# Motores.net
KiCad netlist of a schematic drawn in Altium Designer
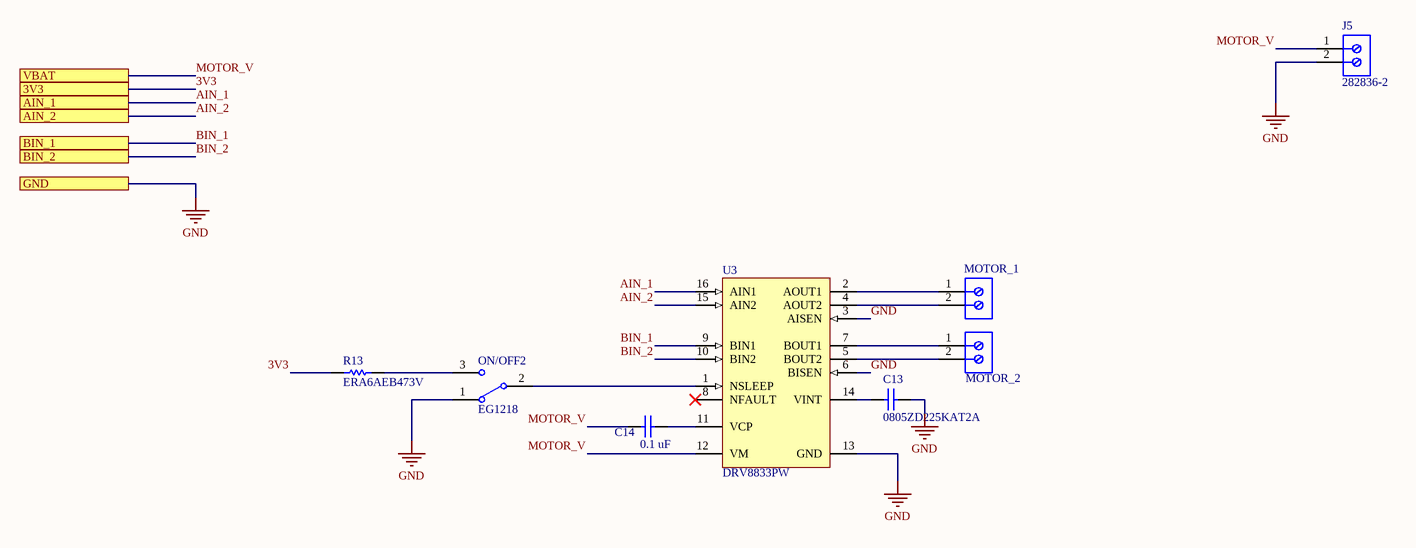
[diagram p0: Motores.SchDoc]

(export (version "E")
  (design (tool "Eeschema 10.0.6"))
  (components
    (comp (ref "C13")
      (value "0805ZD225KAT2A")
      (footprint "CAPC2013X140X50ML20T25")
      (description "Chip Capacitor, 2.2 uF, +/- 10%, 10 V, -55 to 85 degC, 0805 (2012 Metric), RoHS, Tape and Reel")
      (fields (field (name "MANUFACTURER") "AVX"))
      (libsource (lib "Altium Content Vault") (part "CAP-NP-2"))
    )
    (comp (ref "C14")
      (value "0.1 uF")
      (footprint "CAPC2013X94X50ML20T25")
      (description "Chip Capacitor, Ceramic, 0.1 uF, 10%, 50 V, 0805, RoHS, Tape and Reel")
      (fields (field (name "MANUFACTURER") "AVX"))
      (libsource (lib "Altium Content Vault") (part "CAP-NP-2"))
    )
    (comp (ref "J5")
      (value "282836-2")
      (footprint "TECO-282836-2_V")
      (description "Female Header, Pitch 5 mm, 1 x 2 Position, Height 10 mm, Tail Length 3.5 mm, Rohs, Bulk")
      (fields (field (name "VOLTAGE") "300V") (field (name "MANUFACTURER") "TE Connectivity"))
      (libsource (lib "Altium Content Vault") (part "CN-1P-F-TB2"))
    )
    (comp (ref "MOTOR_1")
      (value "691214110002")
      (footprint "691214110002")
      (description "Serie 2141 - 3.50 mm Horizontal Entry Modular with Rising Cage Clamp WR-TBL, 2 pin")
      (fields (field (name "MANUFACTURER") "Wurth Elektronik") (field (name "PUBLISHER") "WurthElektronik"))
      (libsource (lib "Altium Content Vault") (part "WE-CN-1P-F-TB2"))
    )
    (comp (ref "MOTOR_2")
      (value "691214110002")
      (footprint "691214110002")
      (description "Serie 2141 - 3.50 mm Horizontal Entry Modular with Rising Cage Clamp WR-TBL, 2 pin")
      (fields (field (name "MANUFACTURER") "Wurth Elektronik") (field (name "PUBLISHER") "WurthElektronik"))
      (libsource (lib "Altium Content Vault") (part "WE-CN-1P-F-TB2"))
    )
    (comp (ref "ON/OFF2")
      (value "EG1218")
      (footprint "ESWI-EG1218_V")
      (description "Slide Switch, 500 V, -20 to 70 degC, 3-Pin THD, RoHS")
      (libsource (lib "Altium Content Vault") (part "SW-SPDT-3_B"))
    )
    (comp (ref "R13")
      (value "ERA6AEB473V")
      (footprint "RESC2013X60X40LL20T25")
      (fields (field (name "MANUFACTURER") "Panasonic"))
      (libsource (lib "Altium Content Vault") (part "RES"))
    )
    (comp (ref "U3")
      (value "DRV8833PW")
      (footprint "PW0016A_M")
      (fields (field (name "MANUFACTURER") "Texas Instruments"))
      (libsource (lib "Altium Content Vault") (part "TI-DRV8833PW-16"))
    )
  )
  (nets
    (net (code "1") (name "/3V3") (class "Default")
      (node (ref "R13") (pin "2") (pinfunction "2_2") (pintype "passive"))
    )
    (net (code "2") (name "/AIN_1") (class "Default")
      (node (ref "U3") (pin "16") (pinfunction "AIN1_16") (pintype "input"))
    )
    (net (code "3") (name "/AIN_2") (class "Default")
      (node (ref "U3") (pin "15") (pinfunction "AIN2_15") (pintype "input"))
    )
    (net (code "4") (name "/BIN_1") (class "Default")
      (node (ref "U3") (pin "9") (pinfunction "BIN1_9") (pintype "input"))
    )
    (net (code "5") (name "/BIN_2") (class "Default")
      (node (ref "U3") (pin "10") (pinfunction "BIN2_10") (pintype "input"))
    )
    (net (code "6") (name "/MOTOR_V") (class "Default")
      (node (ref "C14") (pin "2") (pinfunction "2_2") (pintype "passive"))
      (node (ref "J5") (pin "1") (pinfunction "1_1") (pintype "passive"))
      (node (ref "U3") (pin "12") (pinfunction "VM_12") (pintype "power_in"))
    )
    (net (code "7") (name "GND") (class "Default")
      (node (ref "C13") (pin "2") (pinfunction "2_2") (pintype "passive"))
      (node (ref "J5") (pin "2") (pinfunction "2_2") (pintype "passive"))
      (node (ref "ON/OFF2") (pin "1") (pinfunction "1_1") (pintype "passive"))
      (node (ref "U3") (pin "13") (pinfunction "GND_13") (pintype "power_in"))
      (node (ref "U3") (pin "3") (pinfunction "AISEN_3") (pintype "input"))
      (node (ref "U3") (pin "6") (pinfunction "BISEN_6") (pintype "input"))
    )
    (net (code "8") (name "Net-(ON/OFF2-COM)") (class "Default")
      (node (ref "ON/OFF2") (pin "2") (pinfunction "COM_2") (pintype "passive"))
      (node (ref "U3") (pin "1") (pinfunction "NSLEEP_1") (pintype "input"))
    )
    (net (code "9") (name "Net-(ON/OFF2-Pad3)") (class "Default")
      (node (ref "ON/OFF2") (pin "3") (pinfunction "3_3") (pintype "passive"))
      (node (ref "R13") (pin "1") (pinfunction "1_1") (pintype "passive"))
    )
    (net (code "10") (name "Net-(U3-AOUT1)") (class "Default")
      (node (ref "MOTOR_1") (pin "1") (pinfunction "1_1") (pintype "passive"))
      (node (ref "U3") (pin "2") (pinfunction "AOUT1_2") (pintype "tri_state"))
    )
    (net (code "11") (name "Net-(U3-AOUT2)") (class "Default")
      (node (ref "MOTOR_1") (pin "2") (pinfunction "2_2") (pintype "passive"))
      (node (ref "U3") (pin "4") (pinfunction "AOUT2_4") (pintype "tri_state"))
    )
    (net (code "12") (name "Net-(U3-BOUT1)") (class "Default")
      (node (ref "MOTOR_2") (pin "1") (pinfunction "1_1") (pintype "passive"))
      (node (ref "U3") (pin "7") (pinfunction "BOUT1_7") (pintype "tri_state"))
    )
    (net (code "13") (name "Net-(U3-BOUT2)") (class "Default")
      (node (ref "MOTOR_2") (pin "2") (pinfunction "2_2") (pintype "passive"))
      (node (ref "U3") (pin "5") (pinfunction "BOUT2_5") (pintype "tri_state"))
    )
    (net (code "14") (name "Net-(U3-VCP)") (class "Default")
      (node (ref "C14") (pin "1") (pinfunction "1_1") (pintype "passive"))
      (node (ref "U3") (pin "11") (pinfunction "VCP_11") (pintype "passive"))
    )
    (net (code "15") (name "Net-(U3-VINT)") (class "Default")
      (node (ref "C13") (pin "1") (pinfunction "1_1") (pintype "passive"))
      (node (ref "U3") (pin "14") (pinfunction "VINT_14") (pintype "passive"))
    )
    (net (code "16") (name "unconnected-(U3-NFAULT-Pad8)") (class "Default")
      (node (ref "U3") (pin "8") (pinfunction "NFAULT_8") (pintype "open_collector+no_connect"))
    )
  )
)
